# Peripheral.net
KiCad netlist of a schematic drawn in Altium Designer
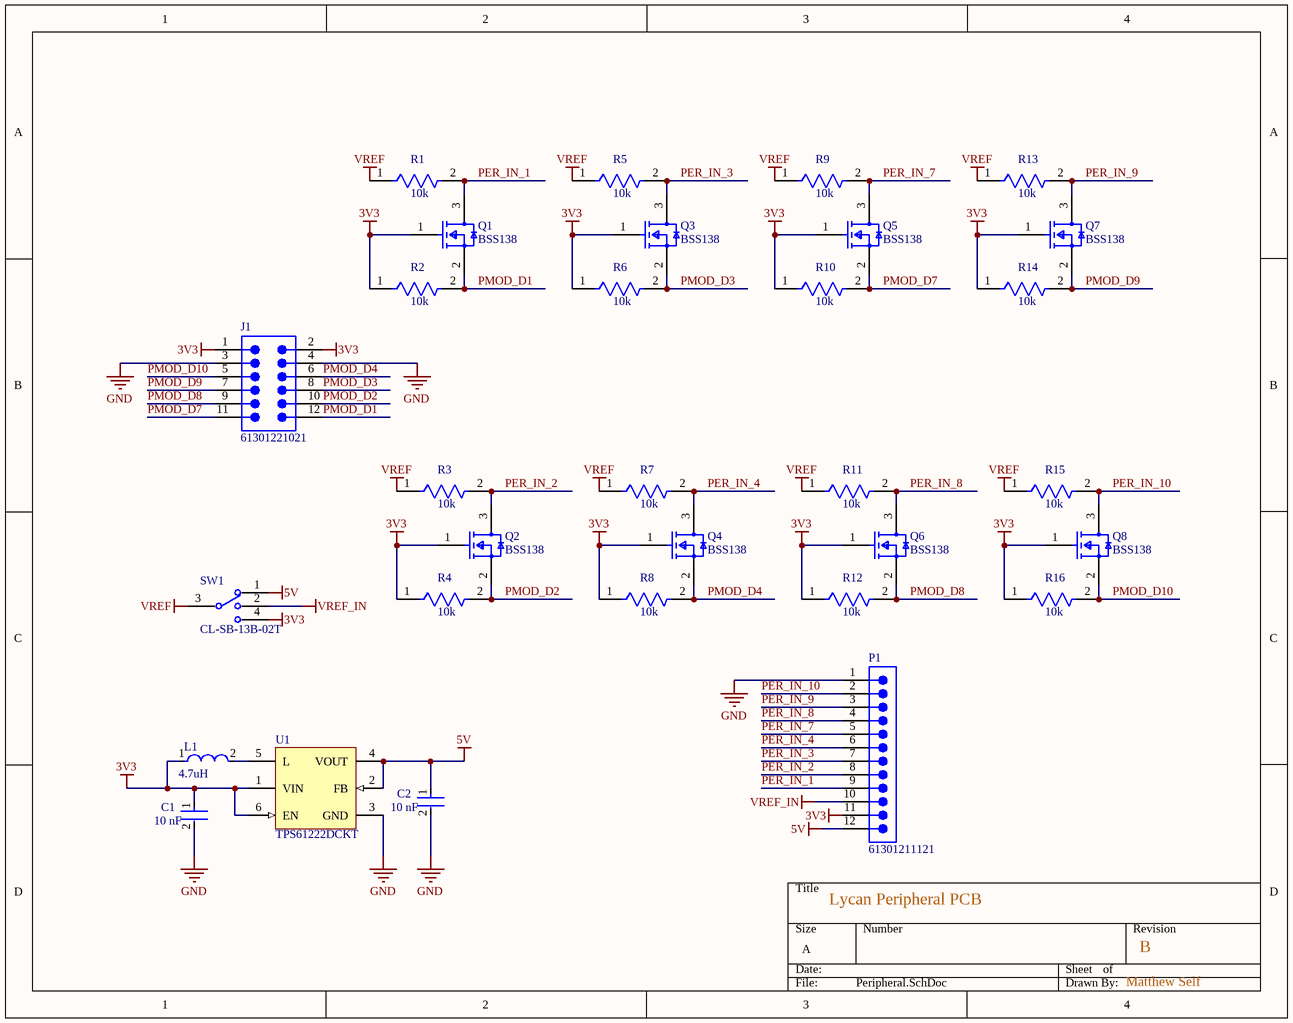
[diagram p0: Peripheral.SchDoc]

(export (version "E")
  (design (tool "Eeschema 10.0.6"))
  (components
    (comp (ref "C1")
      (value "CC1206KRX7R9BB103")
      (footprint "FP-CC1206-1_25-MFG")
      (description "CAP CER 10000PF 50V X7R 1206")
      (fields
        (field (name "OCTOPART") "https://octopart.com/cc1206krx7r9bb103-yageo-39467800")
        (field (name "TOLERANCE") "0.1")
        (field (name "CAPACITANCE") "10 nF")
      )
      (libsource (lib "Altium Content Vault") (part "11868f565c42a9108669ba33697ecf6"))
    )
    (comp (ref "C2")
      (value "CC1206KRX7R9BB103")
      (footprint "FP-CC1206-1_25-MFG")
      (description "CAP CER 10000PF 50V X7R 1206")
      (fields
        (field (name "OCTOPART") "https://octopart.com/cc1206krx7r9bb103-yageo-39467800")
        (field (name "TOLERANCE") "0.1")
        (field (name "CAPACITANCE") "10 nF")
      )
      (libsource (lib "Altium Content Vault") (part "11868f565c42a9108669ba33697ecf6"))
    )
    (comp (ref "J1")
      (value "61301221021")
      (footprint "61301221021")
      (libsource (lib "Altium Content Vault") (part "Header_Male_2R_12P"))
    )
    (comp (ref "L1")
      (value "LQM2HPN4R7MG0L")
      (footprint "FP-LQM2HPN_G0-IPC_A")
      (description "Multilayer Type Inductor for Power Lines, 1008 (2520), 4.7μH, 20%, 0.138Ω, 1.1A")
      (fields (field (name "TOLERANCE") "20%") (field (name "INDUCTANCE") "4.7uH"))
      (libsource (lib "Altium Content Vault") (part "725321dda6339637d4d059423bc1c3c"))
    )
    (comp (ref "P1")
      (value "61301211121")
      (footprint "61301211121")
      (libsource (lib "Altium Content Vault") (part "Header_Male_1R_12P"))
    )
    (comp (ref "Q1")
      (value "BSS138")
      (footprint "FP-318-08-IPC_B")
      (description "MOSFET N-CH 50V 220MA SOT-23")
      (libsource (lib "Altium Content Vault") (part "3b9c635fedb024a5347a57b145af9cc"))
    )
    (comp (ref "Q2")
      (value "BSS138")
      (footprint "FP-318-08-IPC_B")
      (description "MOSFET N-CH 50V 220MA SOT-23")
      (libsource (lib "Altium Content Vault") (part "3b9c635fedb024a5347a57b145af9cc"))
    )
    (comp (ref "Q3")
      (value "BSS138")
      (footprint "FP-318-08-IPC_B")
      (description "MOSFET N-CH 50V 220MA SOT-23")
      (libsource (lib "Altium Content Vault") (part "3b9c635fedb024a5347a57b145af9cc"))
    )
    (comp (ref "Q4")
      (value "BSS138")
      (footprint "FP-318-08-IPC_B")
      (description "MOSFET N-CH 50V 220MA SOT-23")
      (libsource (lib "Altium Content Vault") (part "3b9c635fedb024a5347a57b145af9cc"))
    )
    (comp (ref "Q5")
      (value "BSS138")
      (footprint "FP-318-08-IPC_B")
      (description "MOSFET N-CH 50V 220MA SOT-23")
      (libsource (lib "Altium Content Vault") (part "3b9c635fedb024a5347a57b145af9cc"))
    )
    (comp (ref "Q6")
      (value "BSS138")
      (footprint "FP-318-08-IPC_B")
      (description "MOSFET N-CH 50V 220MA SOT-23")
      (libsource (lib "Altium Content Vault") (part "3b9c635fedb024a5347a57b145af9cc"))
    )
    (comp (ref "Q7")
      (value "BSS138")
      (footprint "FP-318-08-IPC_B")
      (description "MOSFET N-CH 50V 220MA SOT-23")
      (libsource (lib "Altium Content Vault") (part "3b9c635fedb024a5347a57b145af9cc"))
    )
    (comp (ref "Q8")
      (value "BSS138")
      (footprint "FP-318-08-IPC_B")
      (description "MOSFET N-CH 50V 220MA SOT-23")
      (libsource (lib "Altium Content Vault") (part "3b9c635fedb024a5347a57b145af9cc"))
    )
    (comp (ref "R1")
      (value "CR1206-JW-103ELF")
      (footprint "FP-CR1206-IPC_B")
      (description "Thick Film Chip Resistors 1206 10kΩ 0.25W 5% 200ppm/°C")
      (fields (field (name "RESISTANCE") "10k") (field (name "TOLERANCE") "5%"))
      (libsource (lib "Altium Content Vault") (part "1029c3af85768c4190bb7ad29bc67b5"))
    )
    (comp (ref "R2")
      (value "CR1206-JW-103ELF")
      (footprint "FP-CR1206-IPC_B")
      (description "Thick Film Chip Resistors 1206 10kΩ 0.25W 5% 200ppm/°C")
      (fields (field (name "RESISTANCE") "10k") (field (name "TOLERANCE") "5%"))
      (libsource (lib "Altium Content Vault") (part "1029c3af85768c4190bb7ad29bc67b5"))
    )
    (comp (ref "R3")
      (value "CR1206-JW-103ELF")
      (footprint "FP-CR1206-IPC_B")
      (description "Thick Film Chip Resistors 1206 10kΩ 0.25W 5% 200ppm/°C")
      (fields (field (name "RESISTANCE") "10k") (field (name "TOLERANCE") "5%"))
      (libsource (lib "Altium Content Vault") (part "1029c3af85768c4190bb7ad29bc67b5"))
    )
    (comp (ref "R4")
      (value "CR1206-JW-103ELF")
      (footprint "FP-CR1206-IPC_B")
      (description "Thick Film Chip Resistors 1206 10kΩ 0.25W 5% 200ppm/°C")
      (fields (field (name "RESISTANCE") "10k") (field (name "TOLERANCE") "5%"))
      (libsource (lib "Altium Content Vault") (part "1029c3af85768c4190bb7ad29bc67b5"))
    )
    (comp (ref "R5")
      (value "CR1206-JW-103ELF")
      (footprint "FP-CR1206-IPC_B")
      (description "Thick Film Chip Resistors 1206 10kΩ 0.25W 5% 200ppm/°C")
      (fields (field (name "RESISTANCE") "10k") (field (name "TOLERANCE") "5%"))
      (libsource (lib "Altium Content Vault") (part "1029c3af85768c4190bb7ad29bc67b5"))
    )
    (comp (ref "R6")
      (value "CR1206-JW-103ELF")
      (footprint "FP-CR1206-IPC_B")
      (description "Thick Film Chip Resistors 1206 10kΩ 0.25W 5% 200ppm/°C")
      (fields (field (name "RESISTANCE") "10k") (field (name "TOLERANCE") "5%"))
      (libsource (lib "Altium Content Vault") (part "1029c3af85768c4190bb7ad29bc67b5"))
    )
    (comp (ref "R7")
      (value "CR1206-JW-103ELF")
      (footprint "FP-CR1206-IPC_B")
      (description "Thick Film Chip Resistors 1206 10kΩ 0.25W 5% 200ppm/°C")
      (fields (field (name "RESISTANCE") "10k") (field (name "TOLERANCE") "5%"))
      (libsource (lib "Altium Content Vault") (part "1029c3af85768c4190bb7ad29bc67b5"))
    )
    (comp (ref "R8")
      (value "CR1206-JW-103ELF")
      (footprint "FP-CR1206-IPC_B")
      (description "Thick Film Chip Resistors 1206 10kΩ 0.25W 5% 200ppm/°C")
      (fields (field (name "RESISTANCE") "10k") (field (name "TOLERANCE") "5%"))
      (libsource (lib "Altium Content Vault") (part "1029c3af85768c4190bb7ad29bc67b5"))
    )
    (comp (ref "R9")
      (value "CR1206-JW-103ELF")
      (footprint "FP-CR1206-IPC_B")
      (description "Thick Film Chip Resistors 1206 10kΩ 0.25W 5% 200ppm/°C")
      (fields (field (name "RESISTANCE") "10k") (field (name "TOLERANCE") "5%"))
      (libsource (lib "Altium Content Vault") (part "1029c3af85768c4190bb7ad29bc67b5"))
    )
    (comp (ref "R10")
      (value "CR1206-JW-103ELF")
      (footprint "FP-CR1206-IPC_B")
      (description "Thick Film Chip Resistors 1206 10kΩ 0.25W 5% 200ppm/°C")
      (fields (field (name "RESISTANCE") "10k") (field (name "TOLERANCE") "5%"))
      (libsource (lib "Altium Content Vault") (part "1029c3af85768c4190bb7ad29bc67b5"))
    )
    (comp (ref "R11")
      (value "CR1206-JW-103ELF")
      (footprint "FP-CR1206-IPC_B")
      (description "Thick Film Chip Resistors 1206 10kΩ 0.25W 5% 200ppm/°C")
      (fields (field (name "RESISTANCE") "10k") (field (name "TOLERANCE") "5%"))
      (libsource (lib "Altium Content Vault") (part "1029c3af85768c4190bb7ad29bc67b5"))
    )
    (comp (ref "R12")
      (value "CR1206-JW-103ELF")
      (footprint "FP-CR1206-IPC_B")
      (description "Thick Film Chip Resistors 1206 10kΩ 0.25W 5% 200ppm/°C")
      (fields (field (name "RESISTANCE") "10k") (field (name "TOLERANCE") "5%"))
      (libsource (lib "Altium Content Vault") (part "1029c3af85768c4190bb7ad29bc67b5"))
    )
    (comp (ref "R13")
      (value "CR1206-JW-103ELF")
      (footprint "FP-CR1206-IPC_B")
      (description "Thick Film Chip Resistors 1206 10kΩ 0.25W 5% 200ppm/°C")
      (fields (field (name "RESISTANCE") "10k") (field (name "TOLERANCE") "5%"))
      (libsource (lib "Altium Content Vault") (part "1029c3af85768c4190bb7ad29bc67b5"))
    )
    (comp (ref "R14")
      (value "CR1206-JW-103ELF")
      (footprint "FP-CR1206-IPC_B")
      (description "Thick Film Chip Resistors 1206 10kΩ 0.25W 5% 200ppm/°C")
      (fields (field (name "RESISTANCE") "10k") (field (name "TOLERANCE") "5%"))
      (libsource (lib "Altium Content Vault") (part "1029c3af85768c4190bb7ad29bc67b5"))
    )
    (comp (ref "R15")
      (value "CR1206-JW-103ELF")
      (footprint "FP-CR1206-IPC_B")
      (description "Thick Film Chip Resistors 1206 10kΩ 0.25W 5% 200ppm/°C")
      (fields (field (name "RESISTANCE") "10k") (field (name "TOLERANCE") "5%"))
      (libsource (lib "Altium Content Vault") (part "1029c3af85768c4190bb7ad29bc67b5"))
    )
    (comp (ref "R16")
      (value "CR1206-JW-103ELF")
      (footprint "FP-CR1206-IPC_B")
      (description "Thick Film Chip Resistors 1206 10kΩ 0.25W 5% 200ppm/°C")
      (fields (field (name "RESISTANCE") "10k") (field (name "TOLERANCE") "5%"))
      (libsource (lib "Altium Content Vault") (part "1029c3af85768c4190bb7ad29bc67b5"))
    )
    (comp (ref "SW1")
      (value "CL-SB-13B-02T")
      (footprint "FP-CL-SB-13B-02T-MFG")
      (description "CL-SB-13B-02T Switch Slide ON-ON-ON SP3T Top 200mA 12VDC 10000Cycles Gullwing T/R")
      (libsource (lib "Altium Content Vault") (part "5552a05cdd07c74f2f3fb1217988f51"))
    )
    (comp (ref "U1")
      (value "TPS61222DCKT")
      (footprint "DCK0006A_N")
      (fields (field (name "MANUFACTURER") "Texas Instruments"))
      (libsource (lib "Altium Content Vault") (part "TI-TPS61222DCK6"))
    )
  )
  (nets
    (net (code "1") (name "/PER_IN_1") (class "Default")
      (node (ref "P1") (pin "9") (pinfunction "9_9") (pintype "passive"))
      (node (ref "Q1") (pin "3") (pinfunction "D_3") (pintype "passive"))
      (node (ref "R1") (pin "2") (pinfunction "2_2") (pintype "passive"))
    )
    (net (code "2") (name "/PER_IN_2") (class "Default")
      (node (ref "P1") (pin "8") (pinfunction "8_8") (pintype "passive"))
      (node (ref "Q2") (pin "3") (pinfunction "D_3") (pintype "passive"))
      (node (ref "R3") (pin "2") (pinfunction "2_2") (pintype "passive"))
    )
    (net (code "3") (name "/PER_IN_3") (class "Default")
      (node (ref "P1") (pin "7") (pinfunction "7_7") (pintype "passive"))
      (node (ref "Q3") (pin "3") (pinfunction "D_3") (pintype "passive"))
      (node (ref "R5") (pin "2") (pinfunction "2_2") (pintype "passive"))
    )
    (net (code "4") (name "/PER_IN_4") (class "Default")
      (node (ref "P1") (pin "6") (pinfunction "6_6") (pintype "passive"))
      (node (ref "Q4") (pin "3") (pinfunction "D_3") (pintype "passive"))
      (node (ref "R7") (pin "2") (pinfunction "2_2") (pintype "passive"))
    )
    (net (code "5") (name "/PER_IN_7") (class "Default")
      (node (ref "P1") (pin "5") (pinfunction "5_5") (pintype "passive"))
      (node (ref "Q5") (pin "3") (pinfunction "D_3") (pintype "passive"))
      (node (ref "R9") (pin "2") (pinfunction "2_2") (pintype "passive"))
    )
    (net (code "6") (name "/PER_IN_8") (class "Default")
      (node (ref "P1") (pin "4") (pinfunction "4_4") (pintype "passive"))
      (node (ref "Q6") (pin "3") (pinfunction "D_3") (pintype "passive"))
      (node (ref "R11") (pin "2") (pinfunction "2_2") (pintype "passive"))
    )
    (net (code "7") (name "/PER_IN_9") (class "Default")
      (node (ref "P1") (pin "3") (pinfunction "3_3") (pintype "passive"))
      (node (ref "Q7") (pin "3") (pinfunction "D_3") (pintype "passive"))
      (node (ref "R13") (pin "2") (pinfunction "2_2") (pintype "passive"))
    )
    (net (code "8") (name "/PER_IN_10") (class "Default")
      (node (ref "P1") (pin "2") (pinfunction "2_2") (pintype "passive"))
      (node (ref "Q8") (pin "3") (pinfunction "D_3") (pintype "passive"))
      (node (ref "R15") (pin "2") (pinfunction "2_2") (pintype "passive"))
    )
    (net (code "9") (name "/PMOD_D1") (class "Default")
      (node (ref "J1") (pin "12") (pinfunction "12_12") (pintype "passive"))
      (node (ref "Q1") (pin "2") (pinfunction "S_2") (pintype "passive"))
      (node (ref "R2") (pin "2") (pinfunction "2_2") (pintype "passive"))
    )
    (net (code "10") (name "/PMOD_D2") (class "Default")
      (node (ref "J1") (pin "10") (pinfunction "10_10") (pintype "passive"))
      (node (ref "Q2") (pin "2") (pinfunction "S_2") (pintype "passive"))
      (node (ref "R4") (pin "2") (pinfunction "2_2") (pintype "passive"))
    )
    (net (code "11") (name "/PMOD_D3") (class "Default")
      (node (ref "J1") (pin "8") (pinfunction "8_8") (pintype "passive"))
      (node (ref "Q3") (pin "2") (pinfunction "S_2") (pintype "passive"))
      (node (ref "R6") (pin "2") (pinfunction "2_2") (pintype "passive"))
    )
    (net (code "12") (name "/PMOD_D4") (class "Default")
      (node (ref "J1") (pin "6") (pinfunction "6_6") (pintype "passive"))
      (node (ref "Q4") (pin "2") (pinfunction "S_2") (pintype "passive"))
      (node (ref "R8") (pin "2") (pinfunction "2_2") (pintype "passive"))
    )
    (net (code "13") (name "/PMOD_D7") (class "Default")
      (node (ref "J1") (pin "11") (pinfunction "11_11") (pintype "passive"))
      (node (ref "Q5") (pin "2") (pinfunction "S_2") (pintype "passive"))
      (node (ref "R10") (pin "2") (pinfunction "2_2") (pintype "passive"))
    )
    (net (code "14") (name "/PMOD_D8") (class "Default")
      (node (ref "J1") (pin "9") (pinfunction "9_9") (pintype "passive"))
      (node (ref "Q6") (pin "2") (pinfunction "S_2") (pintype "passive"))
      (node (ref "R12") (pin "2") (pinfunction "2_2") (pintype "passive"))
    )
    (net (code "15") (name "/PMOD_D9") (class "Default")
      (node (ref "J1") (pin "7") (pinfunction "7_7") (pintype "passive"))
      (node (ref "Q7") (pin "2") (pinfunction "S_2") (pintype "passive"))
      (node (ref "R14") (pin "2") (pinfunction "2_2") (pintype "passive"))
    )
    (net (code "16") (name "/PMOD_D10") (class "Default")
      (node (ref "J1") (pin "5") (pinfunction "5_5") (pintype "passive"))
      (node (ref "Q8") (pin "2") (pinfunction "S_2") (pintype "passive"))
      (node (ref "R16") (pin "2") (pinfunction "2_2") (pintype "passive"))
    )
    (net (code "17") (name "3V3") (class "Default")
      (node (ref "C1") (pin "1") (pinfunction "1_1") (pintype "passive"))
      (node (ref "J1") (pin "1") (pinfunction "1_1") (pintype "passive"))
      (node (ref "J1") (pin "2") (pinfunction "2_2") (pintype "passive"))
      (node (ref "L1") (pin "1") (pinfunction "1_1") (pintype "passive"))
      (node (ref "P1") (pin "11") (pinfunction "11_11") (pintype "passive"))
      (node (ref "Q1") (pin "1") (pinfunction "G_1") (pintype "passive"))
      (node (ref "Q2") (pin "1") (pinfunction "G_1") (pintype "passive"))
      (node (ref "Q3") (pin "1") (pinfunction "G_1") (pintype "passive"))
      (node (ref "Q4") (pin "1") (pinfunction "G_1") (pintype "passive"))
      (node (ref "Q5") (pin "1") (pinfunction "G_1") (pintype "passive"))
      (node (ref "Q6") (pin "1") (pinfunction "G_1") (pintype "passive"))
      (node (ref "Q7") (pin "1") (pinfunction "G_1") (pintype "passive"))
      (node (ref "Q8") (pin "1") (pinfunction "G_1") (pintype "passive"))
      (node (ref "R10") (pin "1") (pinfunction "1_1") (pintype "passive"))
      (node (ref "R12") (pin "1") (pinfunction "1_1") (pintype "passive"))
      (node (ref "R14") (pin "1") (pinfunction "1_1") (pintype "passive"))
      (node (ref "R16") (pin "1") (pinfunction "1_1") (pintype "passive"))
      (node (ref "R2") (pin "1") (pinfunction "1_1") (pintype "passive"))
      (node (ref "R4") (pin "1") (pinfunction "1_1") (pintype "passive"))
      (node (ref "R6") (pin "1") (pinfunction "1_1") (pintype "passive"))
      (node (ref "R8") (pin "1") (pinfunction "1_1") (pintype "passive"))
      (node (ref "SW1") (pin "4") (pinfunction "4_4") (pintype "passive"))
      (node (ref "U1") (pin "1") (pinfunction "VIN_1") (pintype "power_in"))
      (node (ref "U1") (pin "6") (pinfunction "EN_6") (pintype "input"))
    )
    (net (code "18") (name "5V") (class "Default")
      (node (ref "C2") (pin "1") (pinfunction "1_1") (pintype "passive"))
      (node (ref "P1") (pin "12") (pinfunction "12_12") (pintype "passive"))
      (node (ref "SW1") (pin "1") (pinfunction "1_1") (pintype "passive"))
      (node (ref "U1") (pin "2") (pinfunction "FB_2") (pintype "input"))
      (node (ref "U1") (pin "4") (pinfunction "VOUT_4") (pintype "power_in"))
    )
    (net (code "19") (name "GND") (class "Default")
      (node (ref "C1") (pin "2") (pinfunction "2_2") (pintype "passive"))
      (node (ref "C2") (pin "2") (pinfunction "2_2") (pintype "passive"))
      (node (ref "J1") (pin "3") (pinfunction "3_3") (pintype "passive"))
      (node (ref "J1") (pin "4") (pinfunction "4_4") (pintype "passive"))
      (node (ref "P1") (pin "1") (pinfunction "1_1") (pintype "passive"))
      (node (ref "U1") (pin "3") (pinfunction "GND_3") (pintype "power_in"))
    )
    (net (code "20") (name "Net-(U1-L)") (class "Default")
      (node (ref "L1") (pin "2") (pinfunction "2_2") (pintype "passive"))
      (node (ref "U1") (pin "5") (pinfunction "L_5") (pintype "power_in"))
    )
    (net (code "21") (name "VREF") (class "Default")
      (node (ref "R1") (pin "1") (pinfunction "1_1") (pintype "passive"))
      (node (ref "R11") (pin "1") (pinfunction "1_1") (pintype "passive"))
      (node (ref "R13") (pin "1") (pinfunction "1_1") (pintype "passive"))
      (node (ref "R15") (pin "1") (pinfunction "1_1") (pintype "passive"))
      (node (ref "R3") (pin "1") (pinfunction "1_1") (pintype "passive"))
      (node (ref "R5") (pin "1") (pinfunction "1_1") (pintype "passive"))
      (node (ref "R7") (pin "1") (pinfunction "1_1") (pintype "passive"))
      (node (ref "R9") (pin "1") (pinfunction "1_1") (pintype "passive"))
      (node (ref "SW1") (pin "3") (pinfunction "C_3") (pintype "passive"))
    )
    (net (code "22") (name "VREF_IN") (class "Default")
      (node (ref "P1") (pin "10") (pinfunction "10_10") (pintype "passive"))
      (node (ref "SW1") (pin "2") (pinfunction "2_2") (pintype "passive"))
    )
  )
)
